# stabilizator.net
KiCad netlist of a schematic drawn in EAGLE
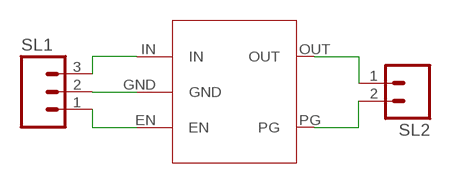
[diagram p0: schematic, sheet 1]

(export (version "E")
  (design (tool "Eeschema 10.0.6"))
  (components
    (comp (ref "SL1")
      (value "MA03")
      (footprint "eagle-import:03P")
      (libsource (lib "eagle-import") (part "MA03"))
    )
    (comp (ref "SL2")
      (value "MA02")
      (footprint "eagle-import:02PA")
      (libsource (lib "eagle-import") (part "MA02"))
    )
    (comp (ref "U$1")
      (value "LDLN030")
      (footprint "eagle-import:LDLN030")
      (libsource (lib "eagle-import") (part "LDLN030"))
    )
  )
  (nets
    (net (code "1") (name "Net-(SL1-Pad1)") (class "Default")
      (node (ref "SL1") (pin "1") (pinfunction "1_1") (pintype "passive"))
      (node (ref "U$1") (pin "EN") (pinfunction "EN_EN") (pintype "bidirectional"))
    )
    (net (code "2") (name "Net-(SL1-Pad2)") (class "Default")
      (node (ref "SL1") (pin "2") (pinfunction "2_2") (pintype "passive"))
      (node (ref "U$1") (pin "GND") (pinfunction "GND_GND") (pintype "bidirectional"))
    )
    (net (code "3") (name "Net-(SL1-Pad3)") (class "Default")
      (node (ref "SL1") (pin "3") (pinfunction "3_3") (pintype "passive"))
      (node (ref "U$1") (pin "IN") (pinfunction "IN_IN") (pintype "bidirectional"))
    )
    (net (code "4") (name "Net-(SL2-Pad1)") (class "Default")
      (node (ref "SL2") (pin "1") (pinfunction "1_1") (pintype "passive"))
      (node (ref "U$1") (pin "OUT") (pinfunction "OUT_OUT") (pintype "bidirectional"))
    )
    (net (code "5") (name "Net-(SL2-Pad2)") (class "Default")
      (node (ref "SL2") (pin "2") (pinfunction "2_2") (pintype "passive"))
      (node (ref "U$1") (pin "PG") (pinfunction "PG_PG") (pintype "bidirectional"))
    )
  )
)
